# osc_devre.net
KiCad netlist of a schematic drawn in EAGLE
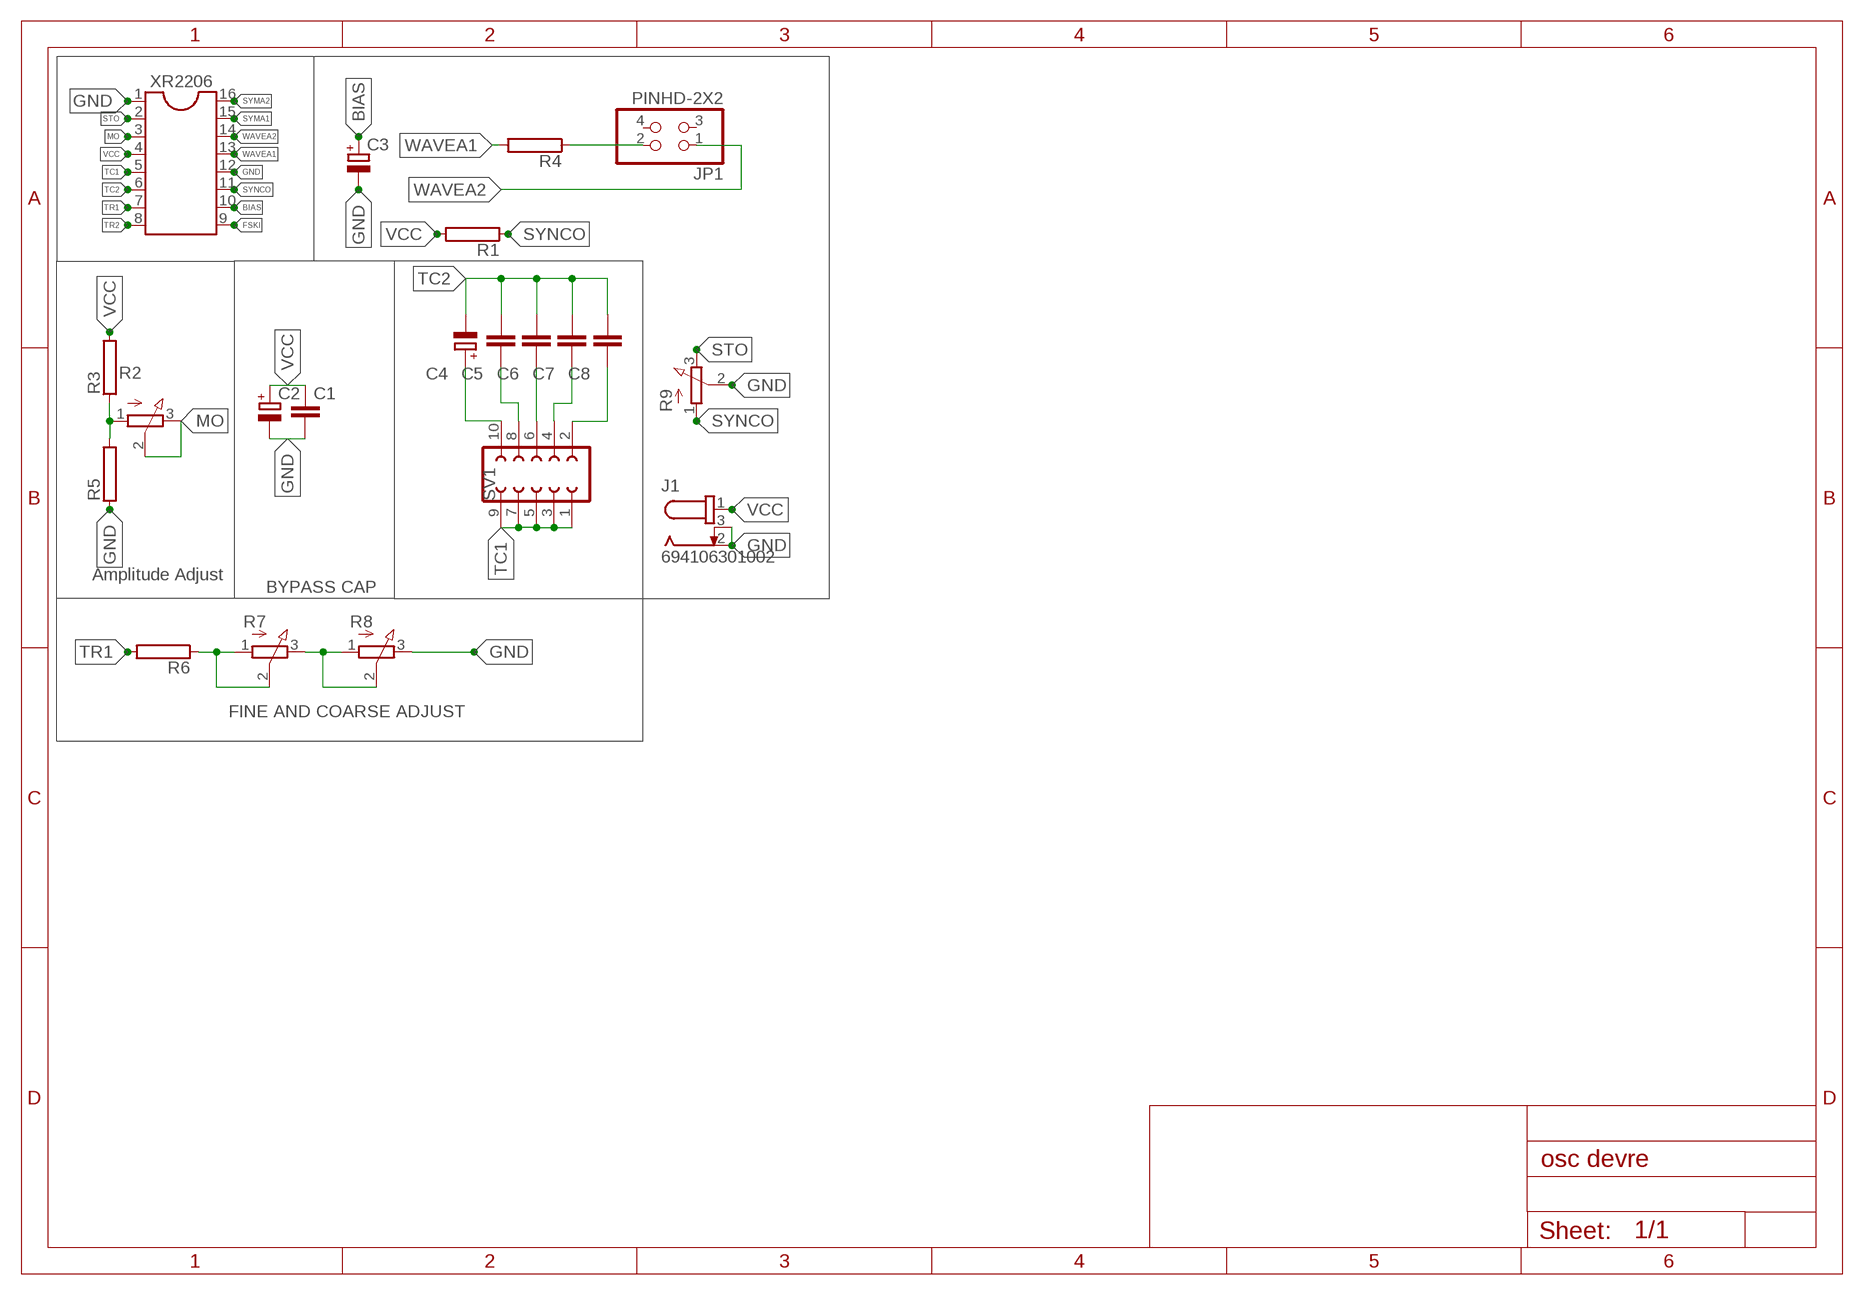
[diagram p0: schematic, sheet 1]

(export (version "E")
  (design (tool "Eeschema 10.0.6"))
  (components
    (comp (ref "C1")
      (value "C5/3")
      (footprint "eagle-import:C5B3")
      (libsource (lib "eagle-import") (part "C5/3"))
    )
    (comp (ref "C2")
      (value "C-POL_RADIAL-11MM-DIA")
      (footprint "eagle-import:CAPPRD508W65D1000H1100B")
      (libsource (lib "eagle-import") (part "C-POLRADIAL-11MM-DIA_"))
    )
    (comp (ref "C3")
      (value "C-POL_RADIAL-11MM-DIA")
      (footprint "eagle-import:CAPPRD508W65D1000H1100B")
      (libsource (lib "eagle-import") (part "C-POLRADIAL-11MM-DIA_"))
    )
    (comp (ref "C4")
      (value "CPOL-EUE2.5-5")
      (footprint "eagle-import:E2,5-5")
      (libsource (lib "eagle-import") (part "CPOL-EUE2.5-5"))
    )
    (comp (ref "C5")
      (value "C5/3")
      (footprint "eagle-import:C5B3")
      (libsource (lib "eagle-import") (part "C5/3"))
    )
    (comp (ref "C6")
      (value "C5/3")
      (footprint "eagle-import:C5B3")
      (libsource (lib "eagle-import") (part "C5/3"))
    )
    (comp (ref "C7")
      (value "C5/3")
      (footprint "eagle-import:C5B3")
      (libsource (lib "eagle-import") (part "C5/3"))
    )
    (comp (ref "C8")
      (value "C5/3")
      (footprint "eagle-import:C5B3")
      (libsource (lib "eagle-import") (part "C5/3"))
    )
    (comp (ref "J1")
      (value "694106301002")
      (footprint "eagle-import:694106301002")
      (fields
        (field (name "DIGIKEY_PART_NUMBER") "732-5930-ND")
        (field (name "MANUFACTURER") "Wurth Electronics Inc.")
        (field (name "CREATED_BY") "PCBLayout.com")
      )
      (libsource (lib "eagle-import") (part "694106301002"))
    )
    (comp (ref "JP1")
      (value "PINHD-2X2")
      (footprint "eagle-import:2X02")
      (libsource (lib "eagle-import") (part "PINHD-2X2"))
    )
    (comp (ref "R1")
      (value "RCA0001")
      (footprint "eagle-import:CA0001")
      (libsource (lib "eagle-import") (part "RCA0001"))
    )
    (comp (ref "R2")
      (value "3RP/1610N")
      (footprint "eagle-import:3RP_1610N")
      (libsource (lib "eagle-import") (part "3RP/1610N"))
    )
    (comp (ref "R3")
      (value "RCA0001")
      (footprint "eagle-import:CA0001")
      (libsource (lib "eagle-import") (part "RCA0001"))
    )
    (comp (ref "R4")
      (value "RCA0001")
      (footprint "eagle-import:CA0001")
      (libsource (lib "eagle-import") (part "RCA0001"))
    )
    (comp (ref "R5")
      (value "RCA0001")
      (footprint "eagle-import:CA0001")
      (libsource (lib "eagle-import") (part "RCA0001"))
    )
    (comp (ref "R6")
      (value "RCA0001")
      (footprint "eagle-import:CA0001")
      (libsource (lib "eagle-import") (part "RCA0001"))
    )
    (comp (ref "R7")
      (value "3RP/1610N")
      (footprint "eagle-import:3RP_1610N")
      (libsource (lib "eagle-import") (part "3RP/1610N"))
    )
    (comp (ref "R8")
      (value "3RP/1610N")
      (footprint "eagle-import:3RP_1610N")
      (libsource (lib "eagle-import") (part "3RP/1610N"))
    )
    (comp (ref "R9")
      (value "3RP/1610N")
      (footprint "eagle-import:3RP_1610N")
      (libsource (lib "eagle-import") (part "3RP/1610N"))
    )
    (comp (ref "SV1")
      (value "FE05-2")
      (footprint "eagle-import:FE05-2")
      (libsource (lib "eagle-import") (part "FE05-2"))
    )
    (comp (ref "XR2206")
      (value "DIL16")
      (footprint "eagle-import:DIL16")
      (libsource (lib "eagle-import") (part "DIL16"))
    )
  )
  (nets
    (net (code "1") (name "BIAS") (class "Default")
      (node (ref "C3") (pin "1") (pinfunction "+_1") (pintype "passive"))
      (node (ref "XR2206") (pin "10") (pinfunction "10_10") (pintype "passive"))
    )
    (net (code "2") (name "FSKI") (class "Default")
      (node (ref "XR2206") (pin "9") (pinfunction "9_9") (pintype "passive"))
    )
    (net (code "3") (name "GND") (class "Default")
      (node (ref "C1") (pin "2") (pinfunction "2_2") (pintype "passive"))
      (node (ref "C2") (pin "2") (pinfunction "-_2") (pintype "passive"))
      (node (ref "C3") (pin "2") (pinfunction "-_2") (pintype "passive"))
      (node (ref "J1") (pin "2") (pinfunction "2_2") (pintype "passive"))
      (node (ref "J1") (pin "3") (pinfunction "3_3") (pintype "passive"))
      (node (ref "R5") (pin "1") (pinfunction "1_1") (pintype "passive"))
      (node (ref "R8") (pin "3") (pinfunction "E_3") (pintype "passive"))
      (node (ref "R9") (pin "2") (pinfunction "S_2") (pintype "passive"))
      (node (ref "XR2206") (pin "1") (pinfunction "1_1") (pintype "passive"))
      (node (ref "XR2206") (pin "12") (pinfunction "12_12") (pintype "passive"))
    )
    (net (code "4") (name "MO") (class "Default")
      (node (ref "R2") (pin "2") (pinfunction "S_2") (pintype "passive"))
      (node (ref "R2") (pin "3") (pinfunction "E_3") (pintype "passive"))
      (node (ref "XR2206") (pin "3") (pinfunction "3_3") (pintype "passive"))
    )
    (net (code "5") (name "Net-(C4-Pad+)") (class "Default")
      (node (ref "C4") (pin "+") (pinfunction "+_+") (pintype "passive"))
      (node (ref "SV1") (pin "10") (pinfunction "10_10") (pintype "passive"))
    )
    (net (code "6") (name "Net-(C5-Pad1)") (class "Default")
      (node (ref "C5") (pin "1") (pinfunction "1_1") (pintype "passive"))
      (node (ref "SV1") (pin "8") (pinfunction "8_8") (pintype "passive"))
    )
    (net (code "7") (name "Net-(C6-Pad1)") (class "Default")
      (node (ref "C6") (pin "1") (pinfunction "1_1") (pintype "passive"))
      (node (ref "SV1") (pin "6") (pinfunction "6_6") (pintype "passive"))
    )
    (net (code "8") (name "Net-(C7-Pad1)") (class "Default")
      (node (ref "C7") (pin "1") (pinfunction "1_1") (pintype "passive"))
      (node (ref "SV1") (pin "4") (pinfunction "4_4") (pintype "passive"))
    )
    (net (code "9") (name "Net-(C8-Pad1)") (class "Default")
      (node (ref "C8") (pin "1") (pinfunction "1_1") (pintype "passive"))
      (node (ref "SV1") (pin "2") (pinfunction "2_2") (pintype "passive"))
    )
    (net (code "10") (name "Net-(JP1-Pad2)") (class "Default")
      (node (ref "JP1") (pin "2") (pinfunction "2_2") (pintype "passive"))
      (node (ref "R4") (pin "1") (pinfunction "1_1") (pintype "passive"))
    )
    (net (code "11") (name "Net-(R2-A)") (class "Default")
      (node (ref "R2") (pin "1") (pinfunction "A_1") (pintype "passive"))
      (node (ref "R3") (pin "1") (pinfunction "1_1") (pintype "passive"))
      (node (ref "R5") (pin "2") (pinfunction "2_2") (pintype "passive"))
    )
    (net (code "12") (name "Net-(R7-A)") (class "Default")
      (node (ref "R6") (pin "1") (pinfunction "1_1") (pintype "passive"))
      (node (ref "R7") (pin "1") (pinfunction "A_1") (pintype "passive"))
      (node (ref "R7") (pin "2") (pinfunction "S_2") (pintype "passive"))
    )
    (net (code "13") (name "Net-(R7-E)") (class "Default")
      (node (ref "R7") (pin "3") (pinfunction "E_3") (pintype "passive"))
      (node (ref "R8") (pin "1") (pinfunction "A_1") (pintype "passive"))
      (node (ref "R8") (pin "2") (pinfunction "S_2") (pintype "passive"))
    )
    (net (code "14") (name "STO") (class "Default")
      (node (ref "R9") (pin "3") (pinfunction "E_3") (pintype "passive"))
      (node (ref "XR2206") (pin "2") (pinfunction "2_2") (pintype "passive"))
    )
    (net (code "15") (name "SYMA1") (class "Default")
      (node (ref "XR2206") (pin "15") (pinfunction "15_15") (pintype "passive"))
    )
    (net (code "16") (name "SYMA2") (class "Default")
      (node (ref "XR2206") (pin "16") (pinfunction "16_16") (pintype "passive"))
    )
    (net (code "17") (name "SYNCO") (class "Default")
      (node (ref "R1") (pin "1") (pinfunction "1_1") (pintype "passive"))
      (node (ref "R9") (pin "1") (pinfunction "A_1") (pintype "passive"))
      (node (ref "XR2206") (pin "11") (pinfunction "11_11") (pintype "passive"))
    )
    (net (code "18") (name "TC1") (class "Default")
      (node (ref "SV1") (pin "1") (pinfunction "1_1") (pintype "passive"))
      (node (ref "SV1") (pin "3") (pinfunction "3_3") (pintype "passive"))
      (node (ref "SV1") (pin "5") (pinfunction "5_5") (pintype "passive"))
      (node (ref "SV1") (pin "7") (pinfunction "7_7") (pintype "passive"))
      (node (ref "SV1") (pin "9") (pinfunction "9_9") (pintype "passive"))
      (node (ref "XR2206") (pin "5") (pinfunction "5_5") (pintype "passive"))
    )
    (net (code "19") (name "TC2") (class "Default")
      (node (ref "C4") (pin "-") (pinfunction "-_-") (pintype "passive"))
      (node (ref "C5") (pin "2") (pinfunction "2_2") (pintype "passive"))
      (node (ref "C6") (pin "2") (pinfunction "2_2") (pintype "passive"))
      (node (ref "C7") (pin "2") (pinfunction "2_2") (pintype "passive"))
      (node (ref "C8") (pin "2") (pinfunction "2_2") (pintype "passive"))
      (node (ref "XR2206") (pin "6") (pinfunction "6_6") (pintype "passive"))
    )
    (net (code "20") (name "TR1") (class "Default")
      (node (ref "R6") (pin "2") (pinfunction "2_2") (pintype "passive"))
      (node (ref "XR2206") (pin "7") (pinfunction "7_7") (pintype "passive"))
    )
    (net (code "21") (name "TR2") (class "Default")
      (node (ref "XR2206") (pin "8") (pinfunction "8_8") (pintype "passive"))
    )
    (net (code "22") (name "VCC") (class "Default")
      (node (ref "C1") (pin "1") (pinfunction "1_1") (pintype "passive"))
      (node (ref "C2") (pin "1") (pinfunction "+_1") (pintype "passive"))
      (node (ref "J1") (pin "1") (pinfunction "1_1") (pintype "passive"))
      (node (ref "R1") (pin "2") (pinfunction "2_2") (pintype "passive"))
      (node (ref "R3") (pin "2") (pinfunction "2_2") (pintype "passive"))
      (node (ref "XR2206") (pin "4") (pinfunction "4_4") (pintype "passive"))
    )
    (net (code "23") (name "WAVEA1") (class "Default")
      (node (ref "R4") (pin "2") (pinfunction "2_2") (pintype "passive"))
      (node (ref "XR2206") (pin "13") (pinfunction "13_13") (pintype "passive"))
    )
    (net (code "24") (name "WAVEA2") (class "Default")
      (node (ref "JP1") (pin "1") (pinfunction "1_1") (pintype "passive"))
      (node (ref "XR2206") (pin "14") (pinfunction "14_14") (pintype "passive"))
    )
    (net (code "25") (name "unconnected-(JP1-Pad3)") (class "Default")
      (node (ref "JP1") (pin "3") (pinfunction "3_3") (pintype "passive"))
    )
    (net (code "26") (name "unconnected-(JP1-Pad4)") (class "Default")
      (node (ref "JP1") (pin "4") (pinfunction "4_4") (pintype "passive"))
    )
  )
)
